# MSP-EXP430F5529LP_v2.net
KiCad netlist of a schematic drawn in EAGLE
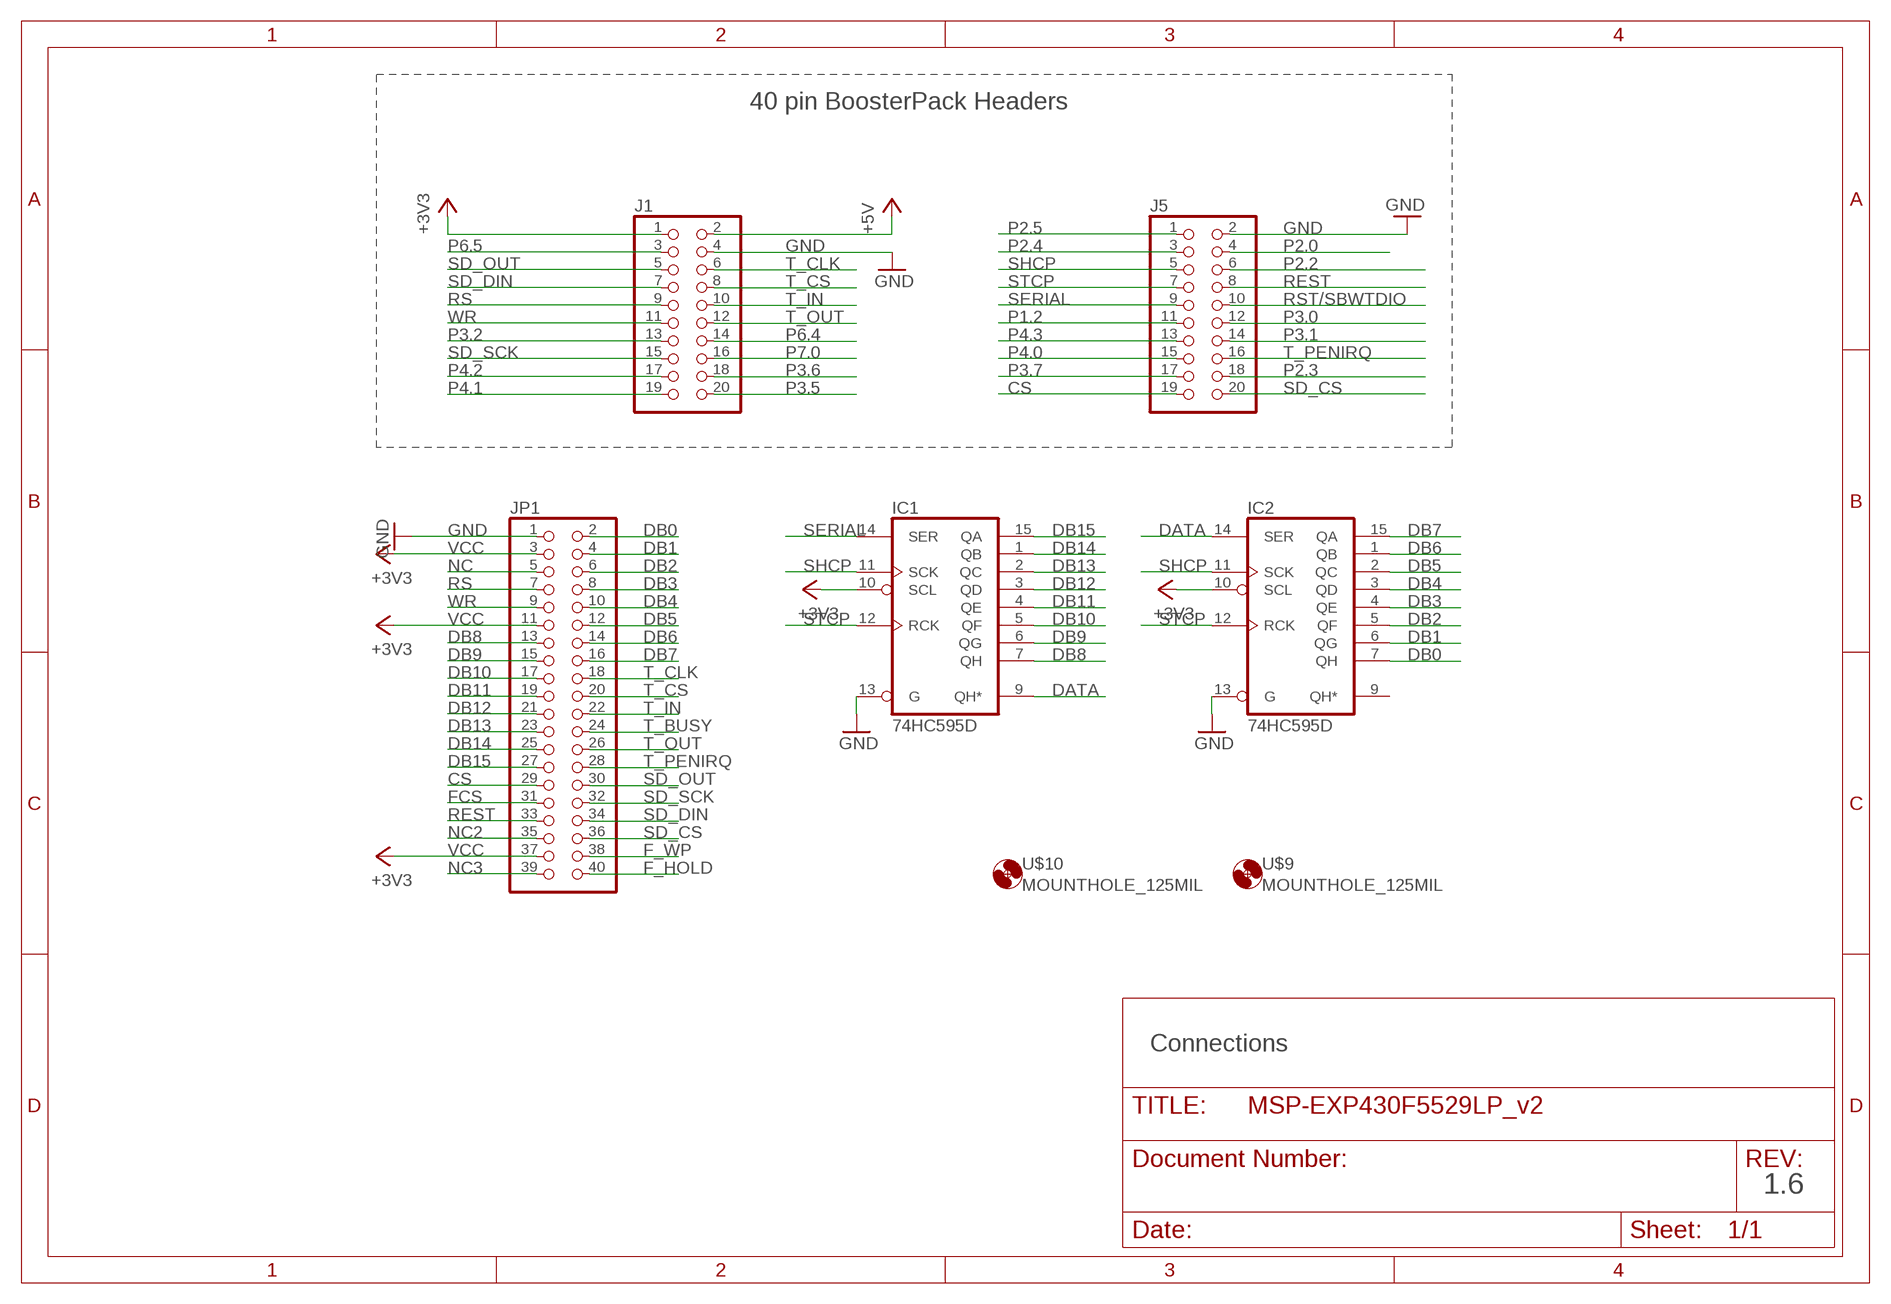
[diagram p0: schematic, sheet 1]

(export (version "E")
  (design (tool "Eeschema 10.0.6"))
  (components
    (comp (ref "IC1")
      (value "74HC595D")
      (footprint "eagle-import:SO16")
      (libsource (lib "eagle-import") (part "74595DHC"))
    )
    (comp (ref "IC2")
      (value "74HC595D")
      (footprint "eagle-import:SO16")
      (libsource (lib "eagle-import") (part "74595DHC"))
    )
    (comp (ref "J1")
      (value "PINHD-2X10")
      (footprint "eagle-import:2X10")
      (libsource (lib "eagle-import") (part "PINHD-2X10"))
    )
    (comp (ref "J5")
      (value "PINHD-2X10")
      (footprint "eagle-import:2X10")
      (libsource (lib "eagle-import") (part "PINHD-2X10"))
    )
    (comp (ref "JP1")
      (value "PINHD-2X20")
      (footprint "eagle-import:2X20")
      (libsource (lib "eagle-import") (part "PINHD-2X20"))
    )
    (comp (ref "U$9")
      (value "MOUNTHOLE_125MIL")
      (footprint "eagle-import:MOUNTHOLE_125MIL")
      (libsource (lib "eagle-import") (part "MOUNTHOLE_125MIL"))
    )
    (comp (ref "U$10")
      (value "MOUNTHOLE_125MIL")
      (footprint "eagle-import:MOUNTHOLE_125MIL")
      (libsource (lib "eagle-import") (part "MOUNTHOLE_125MIL"))
    )
  )
  (nets
    (net (code "1") (name "+3V3") (class "Default")
      (node (ref "IC1") (pin "10") (pinfunction "SCL_10") (pintype "input"))
      (node (ref "IC2") (pin "10") (pinfunction "SCL_10") (pintype "input"))
      (node (ref "J1") (pin "1") (pinfunction "1_1") (pintype "passive"))
      (node (ref "JP1") (pin "11") (pinfunction "11_11") (pintype "passive"))
      (node (ref "JP1") (pin "3") (pinfunction "3_3") (pintype "passive"))
      (node (ref "JP1") (pin "37") (pinfunction "37_37") (pintype "passive"))
    )
    (net (code "2") (name "+5V") (class "Default")
      (node (ref "J1") (pin "2") (pinfunction "2_2") (pintype "passive"))
    )
    (net (code "3") (name "/CS") (class "Default")
      (node (ref "J5") (pin "19") (pinfunction "19_19") (pintype "passive"))
      (node (ref "JP1") (pin "29") (pinfunction "29_29") (pintype "passive"))
    )
    (net (code "4") (name "/DATA") (class "Default")
      (node (ref "IC1") (pin "9") (pinfunction "QH*_9") (pintype "tri_state"))
      (node (ref "IC2") (pin "14") (pinfunction "SER_14") (pintype "input"))
    )
    (net (code "5") (name "/DB0") (class "Default")
      (node (ref "IC2") (pin "7") (pinfunction "QH_7") (pintype "tri_state"))
      (node (ref "JP1") (pin "2") (pinfunction "2_2") (pintype "passive"))
    )
    (net (code "6") (name "/DB1") (class "Default")
      (node (ref "IC2") (pin "6") (pinfunction "QG_6") (pintype "tri_state"))
      (node (ref "JP1") (pin "4") (pinfunction "4_4") (pintype "passive"))
    )
    (net (code "7") (name "/DB2") (class "Default")
      (node (ref "IC2") (pin "5") (pinfunction "QF_5") (pintype "tri_state"))
      (node (ref "JP1") (pin "6") (pinfunction "6_6") (pintype "passive"))
    )
    (net (code "8") (name "/DB3") (class "Default")
      (node (ref "IC2") (pin "4") (pinfunction "QE_4") (pintype "tri_state"))
      (node (ref "JP1") (pin "8") (pinfunction "8_8") (pintype "passive"))
    )
    (net (code "9") (name "/DB4") (class "Default")
      (node (ref "IC2") (pin "3") (pinfunction "QD_3") (pintype "tri_state"))
      (node (ref "JP1") (pin "10") (pinfunction "10_10") (pintype "passive"))
    )
    (net (code "10") (name "/DB5") (class "Default")
      (node (ref "IC2") (pin "2") (pinfunction "QC_2") (pintype "tri_state"))
      (node (ref "JP1") (pin "12") (pinfunction "12_12") (pintype "passive"))
    )
    (net (code "11") (name "/DB6") (class "Default")
      (node (ref "IC2") (pin "1") (pinfunction "QB_1") (pintype "tri_state"))
      (node (ref "JP1") (pin "14") (pinfunction "14_14") (pintype "passive"))
    )
    (net (code "12") (name "/DB7") (class "Default")
      (node (ref "IC2") (pin "15") (pinfunction "QA_15") (pintype "tri_state"))
      (node (ref "JP1") (pin "16") (pinfunction "16_16") (pintype "passive"))
    )
    (net (code "13") (name "/DB8") (class "Default")
      (node (ref "IC1") (pin "7") (pinfunction "QH_7") (pintype "tri_state"))
      (node (ref "JP1") (pin "13") (pinfunction "13_13") (pintype "passive"))
    )
    (net (code "14") (name "/DB9") (class "Default")
      (node (ref "IC1") (pin "6") (pinfunction "QG_6") (pintype "tri_state"))
      (node (ref "JP1") (pin "15") (pinfunction "15_15") (pintype "passive"))
    )
    (net (code "15") (name "/DB10") (class "Default")
      (node (ref "IC1") (pin "5") (pinfunction "QF_5") (pintype "tri_state"))
      (node (ref "JP1") (pin "17") (pinfunction "17_17") (pintype "passive"))
    )
    (net (code "16") (name "/DB11") (class "Default")
      (node (ref "IC1") (pin "4") (pinfunction "QE_4") (pintype "tri_state"))
      (node (ref "JP1") (pin "19") (pinfunction "19_19") (pintype "passive"))
    )
    (net (code "17") (name "/DB12") (class "Default")
      (node (ref "IC1") (pin "3") (pinfunction "QD_3") (pintype "tri_state"))
      (node (ref "JP1") (pin "21") (pinfunction "21_21") (pintype "passive"))
    )
    (net (code "18") (name "/DB13") (class "Default")
      (node (ref "IC1") (pin "2") (pinfunction "QC_2") (pintype "tri_state"))
      (node (ref "JP1") (pin "23") (pinfunction "23_23") (pintype "passive"))
    )
    (net (code "19") (name "/DB14") (class "Default")
      (node (ref "IC1") (pin "1") (pinfunction "QB_1") (pintype "tri_state"))
      (node (ref "JP1") (pin "25") (pinfunction "25_25") (pintype "passive"))
    )
    (net (code "20") (name "/DB15") (class "Default")
      (node (ref "IC1") (pin "15") (pinfunction "QA_15") (pintype "tri_state"))
      (node (ref "JP1") (pin "27") (pinfunction "27_27") (pintype "passive"))
    )
    (net (code "21") (name "/FCS") (class "Default")
      (node (ref "JP1") (pin "31") (pinfunction "31_31") (pintype "passive"))
    )
    (net (code "22") (name "/F_HOLD") (class "Default")
      (node (ref "JP1") (pin "40") (pinfunction "40_40") (pintype "passive"))
    )
    (net (code "23") (name "/F_WP") (class "Default")
      (node (ref "JP1") (pin "38") (pinfunction "38_38") (pintype "passive"))
    )
    (net (code "24") (name "/NC") (class "Default")
      (node (ref "JP1") (pin "5") (pinfunction "5_5") (pintype "passive"))
    )
    (net (code "25") (name "/NC2") (class "Default")
      (node (ref "JP1") (pin "35") (pinfunction "35_35") (pintype "passive"))
    )
    (net (code "26") (name "/NC3") (class "Default")
      (node (ref "JP1") (pin "39") (pinfunction "39_39") (pintype "passive"))
    )
    (net (code "27") (name "/P1.2") (class "Default")
      (node (ref "J5") (pin "11") (pinfunction "11_11") (pintype "passive"))
    )
    (net (code "28") (name "/P2.0") (class "Default")
      (node (ref "J5") (pin "4") (pinfunction "4_4") (pintype "passive"))
    )
    (net (code "29") (name "/P2.2") (class "Default")
      (node (ref "J5") (pin "6") (pinfunction "6_6") (pintype "passive"))
    )
    (net (code "30") (name "/P2.3") (class "Default")
      (node (ref "J5") (pin "18") (pinfunction "18_18") (pintype "passive"))
    )
    (net (code "31") (name "/P2.4") (class "Default")
      (node (ref "J5") (pin "3") (pinfunction "3_3") (pintype "passive"))
    )
    (net (code "32") (name "/P2.5") (class "Default")
      (node (ref "J5") (pin "1") (pinfunction "1_1") (pintype "passive"))
    )
    (net (code "33") (name "/P3.0") (class "Default")
      (node (ref "J5") (pin "12") (pinfunction "12_12") (pintype "passive"))
    )
    (net (code "34") (name "/P3.1") (class "Default")
      (node (ref "J5") (pin "14") (pinfunction "14_14") (pintype "passive"))
    )
    (net (code "35") (name "/P3.2") (class "Default")
      (node (ref "J1") (pin "13") (pinfunction "13_13") (pintype "passive"))
    )
    (net (code "36") (name "/P3.5") (class "Default")
      (node (ref "J1") (pin "20") (pinfunction "20_20") (pintype "passive"))
    )
    (net (code "37") (name "/P3.6") (class "Default")
      (node (ref "J1") (pin "18") (pinfunction "18_18") (pintype "passive"))
    )
    (net (code "38") (name "/P3.7") (class "Default")
      (node (ref "J5") (pin "17") (pinfunction "17_17") (pintype "passive"))
    )
    (net (code "39") (name "/P4.0") (class "Default")
      (node (ref "J5") (pin "15") (pinfunction "15_15") (pintype "passive"))
    )
    (net (code "40") (name "/P4.1") (class "Default")
      (node (ref "J1") (pin "19") (pinfunction "19_19") (pintype "passive"))
    )
    (net (code "41") (name "/P4.2") (class "Default")
      (node (ref "J1") (pin "17") (pinfunction "17_17") (pintype "passive"))
    )
    (net (code "42") (name "/P4.3") (class "Default")
      (node (ref "J5") (pin "13") (pinfunction "13_13") (pintype "passive"))
    )
    (net (code "43") (name "/P6.4") (class "Default")
      (node (ref "J1") (pin "14") (pinfunction "14_14") (pintype "passive"))
    )
    (net (code "44") (name "/P6.5") (class "Default")
      (node (ref "J1") (pin "3") (pinfunction "3_3") (pintype "passive"))
    )
    (net (code "45") (name "/P7.0") (class "Default")
      (node (ref "J1") (pin "16") (pinfunction "16_16") (pintype "passive"))
    )
    (net (code "46") (name "/REST") (class "Default")
      (node (ref "J5") (pin "8") (pinfunction "8_8") (pintype "passive"))
      (node (ref "JP1") (pin "33") (pinfunction "33_33") (pintype "passive"))
    )
    (net (code "47") (name "/RS") (class "Default")
      (node (ref "J1") (pin "9") (pinfunction "9_9") (pintype "passive"))
      (node (ref "JP1") (pin "7") (pinfunction "7_7") (pintype "passive"))
    )
    (net (code "48") (name "/RST{slash}SBWTDIO") (class "Default")
      (node (ref "J5") (pin "10") (pinfunction "10_10") (pintype "passive"))
    )
    (net (code "49") (name "/SD_CS") (class "Default")
      (node (ref "J5") (pin "20") (pinfunction "20_20") (pintype "passive"))
      (node (ref "JP1") (pin "36") (pinfunction "36_36") (pintype "passive"))
    )
    (net (code "50") (name "/SD_DIN") (class "Default")
      (node (ref "J1") (pin "7") (pinfunction "7_7") (pintype "passive"))
      (node (ref "JP1") (pin "34") (pinfunction "34_34") (pintype "passive"))
    )
    (net (code "51") (name "/SD_OUT") (class "Default")
      (node (ref "J1") (pin "5") (pinfunction "5_5") (pintype "passive"))
      (node (ref "JP1") (pin "30") (pinfunction "30_30") (pintype "passive"))
    )
    (net (code "52") (name "/SD_SCK") (class "Default")
      (node (ref "J1") (pin "15") (pinfunction "15_15") (pintype "passive"))
      (node (ref "JP1") (pin "32") (pinfunction "32_32") (pintype "passive"))
    )
    (net (code "53") (name "/SERIAL") (class "Default")
      (node (ref "IC1") (pin "14") (pinfunction "SER_14") (pintype "input"))
      (node (ref "J5") (pin "9") (pinfunction "9_9") (pintype "passive"))
    )
    (net (code "54") (name "/SHCP") (class "Default")
      (node (ref "IC1") (pin "11") (pinfunction "SCK_11") (pintype "input"))
      (node (ref "IC2") (pin "11") (pinfunction "SCK_11") (pintype "input"))
      (node (ref "J5") (pin "5") (pinfunction "5_5") (pintype "passive"))
    )
    (net (code "55") (name "/STCP") (class "Default")
      (node (ref "IC1") (pin "12") (pinfunction "RCK_12") (pintype "input"))
      (node (ref "IC2") (pin "12") (pinfunction "RCK_12") (pintype "input"))
      (node (ref "J5") (pin "7") (pinfunction "7_7") (pintype "passive"))
    )
    (net (code "56") (name "/T_BUSY") (class "Default")
      (node (ref "JP1") (pin "24") (pinfunction "24_24") (pintype "passive"))
    )
    (net (code "57") (name "/T_CLK") (class "Default")
      (node (ref "J1") (pin "6") (pinfunction "6_6") (pintype "passive"))
      (node (ref "JP1") (pin "18") (pinfunction "18_18") (pintype "passive"))
    )
    (net (code "58") (name "/T_CS") (class "Default")
      (node (ref "J1") (pin "8") (pinfunction "8_8") (pintype "passive"))
      (node (ref "JP1") (pin "20") (pinfunction "20_20") (pintype "passive"))
    )
    (net (code "59") (name "/T_IN") (class "Default")
      (node (ref "J1") (pin "10") (pinfunction "10_10") (pintype "passive"))
      (node (ref "JP1") (pin "22") (pinfunction "22_22") (pintype "passive"))
    )
    (net (code "60") (name "/T_OUT") (class "Default")
      (node (ref "J1") (pin "12") (pinfunction "12_12") (pintype "passive"))
      (node (ref "JP1") (pin "26") (pinfunction "26_26") (pintype "passive"))
    )
    (net (code "61") (name "/T_PENIRQ") (class "Default")
      (node (ref "J5") (pin "16") (pinfunction "16_16") (pintype "passive"))
      (node (ref "JP1") (pin "28") (pinfunction "28_28") (pintype "passive"))
    )
    (net (code "62") (name "/WR") (class "Default")
      (node (ref "J1") (pin "11") (pinfunction "11_11") (pintype "passive"))
      (node (ref "JP1") (pin "9") (pinfunction "9_9") (pintype "passive"))
    )
    (net (code "63") (name "GND") (class "Default")
      (node (ref "IC1") (pin "13") (pinfunction "G_13") (pintype "input"))
      (node (ref "IC2") (pin "13") (pinfunction "G_13") (pintype "input"))
      (node (ref "J1") (pin "4") (pinfunction "4_4") (pintype "passive"))
      (node (ref "J5") (pin "2") (pinfunction "2_2") (pintype "passive"))
      (node (ref "JP1") (pin "1") (pinfunction "1_1") (pintype "passive"))
    )
    (net (code "64") (name "unconnected-(IC2A-QH*-Pad9)") (class "Default")
      (node (ref "IC2") (pin "9") (pinfunction "QH*_9") (pintype "tri_state"))
    )
  )
)
